# PWR.net
KiCad netlist of a schematic drawn in Altium Designer
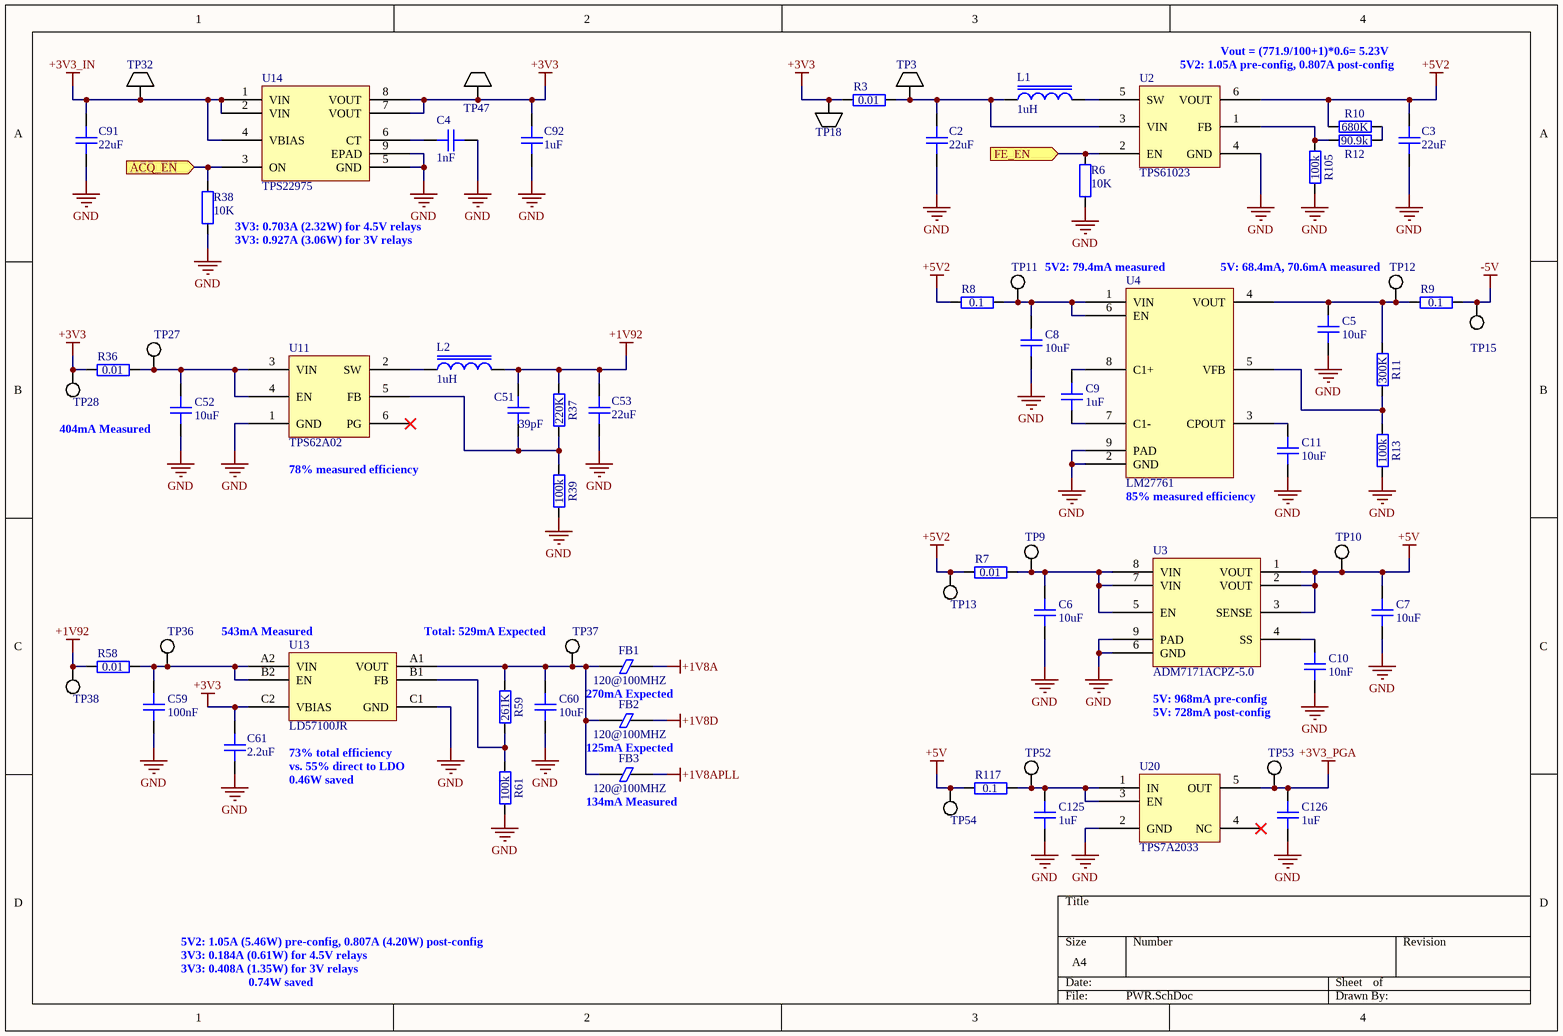
[diagram p0: PWR.SchDoc]

(export (version "E")
  (design (tool "Eeschema 10.0.6"))
  (components
    (comp (ref "C2")
      (value "22uF")
      (footprint "GEN_C_0805")
      (fields
        (field (name "HOUSE PART NUMBER") "C-22uF-0805-002")
        (field (name "MANUFACTURER") "Murata")
        (field (name "MANUFACTURER PART NUMBER") "GRM21BR61E226ME44L")
      )
      (libsource (lib "DSO") (part "CAP 22uF 25V X5R 0805"))
    )
    (comp (ref "C3")
      (value "22uF")
      (footprint "GEN_C_0805")
      (fields
        (field (name "HOUSE PART NUMBER") "C-22uF-0805-002")
        (field (name "MANUFACTURER") "Murata")
        (field (name "MANUFACTURER PART NUMBER") "GRM21BR61E226ME44L")
      )
      (libsource (lib "DSO") (part "CAP 22uF 25V X5R 0805"))
    )
    (comp (ref "C4")
      (value "1nF")
      (footprint "GEN_C_0402")
      (fields
        (field (name "MANUFACTURER") "Murata")
        (field (name "MANUFACTURER PART NUMBER") "GRM1555C1H102FA01D")
      )
      (libsource (lib "DSO") (part "CAP 1nF 50V C0G 0402"))
    )
    (comp (ref "C5")
      (value "10uF")
      (footprint "GEN_C_0603")
      (fields
        (field (name "HOUSE PART NUMBER") "C-10uF-0603-002")
        (field (name "MANUFACTURER") "Murata")
        (field (name "MANUFACTURER PART NUMBER") "GRM188R61A106ME69D")
      )
      (libsource (lib "DSO") (part "CAP 10uF 10V X5R 0603"))
    )
    (comp (ref "C6")
      (value "10uF")
      (footprint "GEN_C_0603")
      (fields
        (field (name "HOUSE PART NUMBER") "C-10uF-0603-002")
        (field (name "MANUFACTURER") "Murata")
        (field (name "MANUFACTURER PART NUMBER") "GRM188R61A106ME69D")
      )
      (libsource (lib "DSO") (part "CAP 10uF 10V X5R 0603"))
    )
    (comp (ref "C7")
      (value "10uF")
      (footprint "GEN_C_0603")
      (fields
        (field (name "HOUSE PART NUMBER") "C-10uF-0603-002")
        (field (name "MANUFACTURER") "Murata")
        (field (name "MANUFACTURER PART NUMBER") "GRM188R61A106ME69D")
      )
      (libsource (lib "DSO") (part "CAP 10uF 10V X5R 0603"))
    )
    (comp (ref "C8")
      (value "10uF")
      (footprint "GEN_C_0603")
      (fields
        (field (name "HOUSE PART NUMBER") "C-10uF-0603-002")
        (field (name "MANUFACTURER") "Murata")
        (field (name "MANUFACTURER PART NUMBER") "GRM188R61A106ME69D")
      )
      (libsource (lib "DSO") (part "CAP 10uF 10V X5R 0603"))
    )
    (comp (ref "C9")
      (value "1uF")
      (footprint "GEN_C_0402")
      (fields
        (field (name "MANUFACTURER") "Murata")
        (field (name "MANUFACTURER PART NUMBER") "GRM155R61E105KA12D")
      )
      (libsource (lib "DSO") (part "CAP 1uF 25V X5R 0402"))
    )
    (comp (ref "C10")
      (value "10nF")
      (footprint "GEN_C_0402")
      (fields
        (field (name "MANUFACTURER") "Murata")
        (field (name "HOUSE PART NUMBER") "C-10nF-0402-002")
        (field (name "MANUFACTURER PART NUMBER") "GRM155R71H103KA88J")
      )
      (libsource (lib "DSO") (part "CAP 10nF 50V X7R 0402"))
    )
    (comp (ref "C11")
      (value "10uF")
      (footprint "GEN_C_0603")
      (fields
        (field (name "HOUSE PART NUMBER") "C-10uF-0603-002")
        (field (name "MANUFACTURER") "Murata")
        (field (name "MANUFACTURER PART NUMBER") "GRM188R61A106ME69D")
      )
      (libsource (lib "DSO") (part "CAP 10uF 10V X5R 0603"))
    )
    (comp (ref "C51")
      (value "39pF")
      (footprint "GEN_C_0402")
      (fields
        (field (name "HOUSE PART NUMBER") "C-39pF-0402-002")
        (field (name "MANUFACTURER") "KEMET")
        (field (name "MANUFACTURER PART NUMBER") "C0402C390J5GACTU")
      )
      (libsource (lib "DSO") (part "CAP 39pF 50V C0G 0402"))
    )
    (comp (ref "C52")
      (value "10uF")
      (footprint "GEN_C_0603")
      (fields
        (field (name "HOUSE PART NUMBER") "C-10uF-0603-002")
        (field (name "MANUFACTURER") "Murata")
        (field (name "MANUFACTURER PART NUMBER") "GRM188R61A106ME69D")
      )
      (libsource (lib "DSO") (part "CAP 10uF 10V X5R 0603"))
    )
    (comp (ref "C53")
      (value "22uF")
      (footprint "GEN_C_0805")
      (fields
        (field (name "HOUSE PART NUMBER") "C-22uF-0805-002")
        (field (name "MANUFACTURER") "Murata")
        (field (name "MANUFACTURER PART NUMBER") "GRM21BR61E226ME44L")
      )
      (libsource (lib "DSO") (part "CAP 22uF 25V X5R 0805"))
    )
    (comp (ref "C59")
      (value "100nF")
      (footprint "GEN_C_0402")
      (fields
        (field (name "HOUSE PART NUMBER") "C-100nF-0402-002")
        (field (name "MANUFACTURER") "Murata")
        (field (name "MANUFACTURER PART NUMBER") "GCM155R71C104KA55D")
      )
      (libsource (lib "DSO") (part "CAP 100nF 16V X7R 0402"))
    )
    (comp (ref "C60")
      (value "10uF")
      (footprint "GEN_C_0603")
      (fields
        (field (name "HOUSE PART NUMBER") "C-10uF-0603-002")
        (field (name "MANUFACTURER") "Murata")
        (field (name "MANUFACTURER PART NUMBER") "GRM188R61A106ME69D")
      )
      (libsource (lib "DSO") (part "CAP 10uF 10V X5R 0603"))
    )
    (comp (ref "C61")
      (value "2.2uF")
      (footprint "GEN_C_0402")
      (fields
        (field (name "MANUFACTURER") "Taiyo Yuden")
        (field (name "MANUFACTURER PART NUMBER") "LMK105BJ225MV-F")
      )
      (libsource (lib "DSO") (part "CAP 2.2uF 10V X5R 0402"))
    )
    (comp (ref "C91")
      (value "22uF")
      (footprint "GEN_C_0805")
      (fields
        (field (name "HOUSE PART NUMBER") "C-22uF-0805-002")
        (field (name "MANUFACTURER") "Murata")
        (field (name "MANUFACTURER PART NUMBER") "GRM21BR61E226ME44L")
      )
      (libsource (lib "DSO") (part "CAP 22uF 25V X5R 0805"))
    )
    (comp (ref "C92")
      (value "1uF")
      (footprint "GEN_C_0402")
      (fields
        (field (name "MANUFACTURER") "Murata")
        (field (name "MANUFACTURER PART NUMBER") "GRM155R61E105KA12D")
      )
      (libsource (lib "DSO") (part "CAP 1uF 25V X5R 0402"))
    )
    (comp (ref "C125")
      (value "1uF")
      (footprint "GEN_C_0402")
      (fields
        (field (name "MANUFACTURER") "Murata")
        (field (name "MANUFACTURER PART NUMBER") "GRM155R61E105KA12D")
      )
      (libsource (lib "DSO") (part "CAP 1uF 25V X5R 0402"))
    )
    (comp (ref "C126")
      (value "1uF")
      (footprint "GEN_C_0402")
      (fields
        (field (name "MANUFACTURER") "Murata")
        (field (name "MANUFACTURER PART NUMBER") "GRM155R61E105KA12D")
      )
      (libsource (lib "DSO") (part "CAP 1uF 25V X5R 0402"))
    )
    (comp (ref "FB1")
      (value "120@100MHZ")
      (footprint "GEN_R_0402")
      (fields (field (name "HOUSE PART NUMBER") "BLM15PX121SN1D") (field (name "MANUFACTURER") "Murata"))
      (libsource (lib "DSO") (part "FERRITE BEAD 120 OHM 0402"))
    )
    (comp (ref "FB2")
      (value "120@100MHZ")
      (footprint "GEN_R_0402")
      (fields (field (name "HOUSE PART NUMBER") "BLM15PX121SN1D") (field (name "MANUFACTURER") "Murata"))
      (libsource (lib "DSO") (part "FERRITE BEAD 120 OHM 0402"))
    )
    (comp (ref "FB3")
      (value "120@100MHZ")
      (footprint "GEN_R_0402")
      (fields (field (name "HOUSE PART NUMBER") "BLM15PX121SN1D") (field (name "MANUFACTURER") "Murata"))
      (libsource (lib "DSO") (part "FERRITE BEAD 120 OHM 0402"))
    )
    (comp (ref "L1")
      (value "1uH")
      (footprint "GEN_L_1210")
      (fields
        (field (name "MANUFACTURER") "Murata")
        (field (name "MANUFACTURER PART NUMBER") "1277AS-H-1R0M=P2")
      )
      (libsource (lib "DSO") (part "IND 1uH 3.1A 45 MOHM 1210"))
    )
    (comp (ref "L2")
      (value "1uH")
      (footprint "GEN_L_1210")
      (fields
        (field (name "MANUFACTURER") "Murata")
        (field (name "MANUFACTURER PART NUMBER") "1277AS-H-1R0M=P2")
      )
      (libsource (lib "DSO") (part "IND 1uH 3.1A 45 MOHM 1210"))
    )
    (comp (ref "R3")
      (value "0.01")
      (footprint "GEN_R_0603")
      (fields
        (field (name "TOLERANCE") "1%")
        (field (name "HOUSE PART NUMBER") "R-0.01-0603-1%-001")
        (field (name "MANUFACTURER") "Susumu")
      )
      (libsource (lib "") (part "RES 0.01 OHM 1% 1/4W 0603_1"))
    )
    (comp (ref "R6")
      (value "10K")
      (footprint "GEN_R_0402")
      (fields
        (field (name "TOLERANCE") "1%")
        (field (name "MANUFACTURER") "Panasonic")
        (field (name "MANUFACTURER PART NUMBER") "ERJ-2RKF1002X")
      )
      (libsource (lib "") (part "RES 10K OHM 1% 1/10W 0402_1"))
    )
    (comp (ref "R7")
      (value "0.01")
      (footprint "GEN_R_0603")
      (fields
        (field (name "TOLERANCE") "1%")
        (field (name "HOUSE PART NUMBER") "R-0.01-0603-1%-001")
        (field (name "MANUFACTURER") "Susumu")
      )
      (libsource (lib "DSO") (part "RES 0.01 OHM 1% 1/4W 0603"))
    )
    (comp (ref "R8")
      (value "0.1")
      (footprint "GEN_R_0402")
      (fields
        (field (name "TOLERANCE") "1%")
        (field (name "MANUFACTURER") "Panasonic")
        (field (name "MANUFACTURER PART NUMBER") "ERJ-2BSFR10X")
      )
      (libsource (lib "DSO") (part "RES 0.1 OHM 1% 1/6W 0402"))
    )
    (comp (ref "R9")
      (value "0.1")
      (footprint "GEN_R_0402")
      (fields
        (field (name "TOLERANCE") "1%")
        (field (name "MANUFACTURER") "Panasonic")
        (field (name "MANUFACTURER PART NUMBER") "ERJ-2BSFR10X")
      )
      (libsource (lib "DSO") (part "RES 0.1 OHM 1% 1/6W 0402"))
    )
    (comp (ref "R10")
      (value "680K")
      (footprint "GEN_R_0402")
      (fields
        (field (name "TOLERANCE") "1%")
        (field (name "MANUFACTURER") "Yageo")
        (field (name "MANUFACTURER PART NUMBER") "RC0402FR-07681KL")
      )
      (libsource (lib "DSO") (part "RES 680K OHM 1% 1/16W 0402"))
    )
    (comp (ref "R11")
      (value "300K")
      (footprint "GEN_R_0402")
      (fields
        (field (name "TOLERANCE") "1%")
        (field (name "MANUFACTURER") "Panasonic")
        (field (name "MANUFACTURER PART NUMBER") "ERJ-2RKF3003X")
      )
      (libsource (lib "DSO") (part "RES 300K OHM 1% 1/10W 0402"))
    )
    (comp (ref "R12")
      (value "90.9k")
      (footprint "GEN_R_0402")
      (fields
        (field (name "TOLERANCE") "1%")
        (field (name "MANUFACTURER") "Yageo")
        (field (name "MANUFACTURER PART NUMBER") "RC0402FR-0790K9L")
      )
      (libsource (lib "DSO") (part "RES 90.9K OHM 1% 1/16W 0402"))
    )
    (comp (ref "R13")
      (value "100k")
      (footprint "GEN_R_0402")
      (fields
        (field (name "TOLERANCE") "1%")
        (field (name "HOUSE PART NUMBER") "R-100K-0402-1%-001")
        (field (name "MANUFACTURER") "Yageo")
      )
      (libsource (lib "DSO") (part "RES 100K OHM 1% 1/10W 0402"))
    )
    (comp (ref "R36")
      (value "0.01")
      (footprint "GEN_R_0603")
      (fields
        (field (name "TOLERANCE") "1%")
        (field (name "HOUSE PART NUMBER") "R-0.01-0603-1%-001")
        (field (name "MANUFACTURER") "Susumu")
      )
      (libsource (lib "DSO") (part "RES 0.01 OHM 1% 1/4W 0603"))
    )
    (comp (ref "R37")
      (value "220K")
      (footprint "GEN_R_0402")
      (fields
        (field (name "TOLERANCE") "1%")
        (field (name "MANUFACTURER") "Yageo")
        (field (name "MANUFACTURER PART NUMBER") "RC0402FR-07220KL")
      )
      (libsource (lib "DSO") (part "RES 220K OHM 1% 1/16W 0402"))
    )
    (comp (ref "R38")
      (value "10K")
      (footprint "GEN_R_0402")
      (fields
        (field (name "TOLERANCE") "1%")
        (field (name "MANUFACTURER") "Panasonic")
        (field (name "MANUFACTURER PART NUMBER") "ERJ-2RKF1002X")
      )
      (libsource (lib "DSO") (part "RES 10K OHM 1% 1/10W 0402"))
    )
    (comp (ref "R39")
      (value "100k")
      (footprint "GEN_R_0402")
      (fields
        (field (name "TOLERANCE") "1%")
        (field (name "HOUSE PART NUMBER") "R-100K-0402-1%-001")
        (field (name "MANUFACTURER") "Yageo")
      )
      (libsource (lib "DSO") (part "RES 100K OHM 1% 1/10W 0402"))
    )
    (comp (ref "R58")
      (value "0.01")
      (footprint "GEN_R_0603")
      (fields
        (field (name "TOLERANCE") "1%")
        (field (name "HOUSE PART NUMBER") "R-0.01-0603-1%-001")
        (field (name "MANUFACTURER") "Susumu")
      )
      (libsource (lib "DSO") (part "RES 0.01 OHM 1% 1/4W 0603"))
    )
    (comp (ref "R59")
      (value "261K")
      (footprint "GEN_R_0402")
      (fields
        (field (name "TOLERANCE") "1%")
        (field (name "MANUFACTURER") "Yageo")
        (field (name "MANUFACTURER PART NUMBER") "RC0402FR-07261KL")
      )
      (libsource (lib "DSO") (part "RES 261K OHM 1% 1/16W 0402"))
    )
    (comp (ref "R61")
      (value "100k")
      (footprint "GEN_R_0402")
      (fields
        (field (name "TOLERANCE") "1%")
        (field (name "HOUSE PART NUMBER") "R-100K-0402-1%-001")
        (field (name "MANUFACTURER") "Yageo")
      )
      (libsource (lib "DSO") (part "RES 100K OHM 1% 1/10W 0402"))
    )
    (comp (ref "R105")
      (value "100k")
      (footprint "GEN_R_0402")
      (fields
        (field (name "TOLERANCE") "1%")
        (field (name "HOUSE PART NUMBER") "R-100K-0402-1%-001")
        (field (name "MANUFACTURER") "Yageo")
      )
      (libsource (lib "DSO") (part "RES 100K OHM 1% 1/10W 0402"))
    )
    (comp (ref "R117")
      (value "0.1")
      (footprint "GEN_R_0402")
      (fields
        (field (name "TOLERANCE") "1%")
        (field (name "MANUFACTURER") "Panasonic")
        (field (name "MANUFACTURER PART NUMBER") "ERJ-2BSFR10X")
      )
      (libsource (lib "DSO") (part "RES 0.1 OHM 1% 1/6W 0402"))
    )
    (comp (ref "TP3")
      (value "5015")
      (footprint "KEY_5015")
      (fields (field (name "MANUFACTURER") "Keystone Electronics"))
      (libsource (lib "DSO") (part "TP KEYSTONE 5015"))
    )
    (comp (ref "TP9") (value "PCB") (footprint "GEN_TP_PCB") (libsource (lib "DSO") (part "TP PCB 1mm")))
    (comp (ref "TP10") (value "PCB") (footprint "GEN_TP_PCB") (libsource (lib "DSO") (part "TP PCB 1mm")))
    (comp (ref "TP11") (value "PCB") (footprint "GEN_TP_PCB") (libsource (lib "DSO") (part "TP PCB 1mm")))
    (comp (ref "TP12") (value "PCB") (footprint "GEN_TP_PCB") (libsource (lib "DSO") (part "TP PCB 1mm")))
    (comp (ref "TP13") (value "PCB") (footprint "GEN_TP_PCB") (libsource (lib "DSO") (part "TP PCB 1mm")))
    (comp (ref "TP15") (value "PCB") (footprint "GEN_TP_PCB") (libsource (lib "DSO") (part "TP PCB 1mm")))
    (comp (ref "TP18")
      (value "5015")
      (footprint "KEY_5015")
      (fields (field (name "MANUFACTURER") "Keystone Electronics"))
      (libsource (lib "DSO") (part "TP KEYSTONE 5015"))
    )
    (comp (ref "TP27") (value "PCB") (footprint "GEN_TP_PCB") (libsource (lib "DSO") (part "TP PCB 1mm")))
    (comp (ref "TP28") (value "PCB") (footprint "GEN_TP_PCB") (libsource (lib "DSO") (part "TP PCB 1mm")))
    (comp (ref "TP32")
      (value "5015")
      (footprint "KEY_5015")
      (fields (field (name "MANUFACTURER") "Keystone Electronics"))
      (libsource (lib "DSO") (part "TP KEYSTONE 5015"))
    )
    (comp (ref "TP36") (value "PCB") (footprint "GEN_TP_PCB") (libsource (lib "DSO") (part "TP PCB 1mm")))
    (comp (ref "TP37") (value "PCB") (footprint "GEN_TP_PCB") (libsource (lib "DSO") (part "TP PCB 1mm")))
    (comp (ref "TP38") (value "PCB") (footprint "GEN_TP_PCB") (libsource (lib "DSO") (part "TP PCB 1mm")))
    (comp (ref "TP47")
      (value "5015")
      (footprint "KEY_5015")
      (fields (field (name "MANUFACTURER") "Keystone Electronics"))
      (libsource (lib "DSO") (part "TP KEYSTONE 5015"))
    )
    (comp (ref "TP52") (value "PCB") (footprint "GEN_TP_PCB") (libsource (lib "DSO") (part "TP PCB 1mm")))
    (comp (ref "TP53") (value "PCB") (footprint "GEN_TP_PCB") (libsource (lib "DSO") (part "TP PCB 1mm")))
    (comp (ref "TP54") (value "PCB") (footprint "GEN_TP_PCB") (libsource (lib "DSO") (part "TP PCB 1mm")))
    (comp (ref "U2")
      (value "TPS61023")
      (footprint "TI_SOT563_DRL0006A")
      (fields
        (field (name "MANUFACTURER") "Texas Instruments")
        (field (name "MANUFACTURER PART NUMBER") "TPS61023DRLT")
      )
      (libsource (lib "DSO") (part "IC BOOST TPS61023"))
    )
    (comp (ref "U3")
      (value "ADM7171ACPZ-5.0")
      (footprint "AD_DFN8_CP-8-21")
      (fields
        (field (name "MANUFACTURER") "Analog Devices")
        (field (name "MANUFACTURER PART NUMBER") "ADM7171ACPZ-5.0-R7")
      )
      (libsource (lib "DSO") (part "IC LDO ADM7171ACPZ-5.0"))
    )
    (comp (ref "U4")
      (value "LM27761")
      (footprint "TI_WSON8_DSG0008A")
      (fields
        (field (name "MANUFACTURER") "Texas Instruments")
        (field (name "MANUFACTURER PART NUMBER") "LM27761DSGR")
      )
      (libsource (lib "DSO") (part "IC CPUMP LM27761"))
    )
    (comp (ref "U11")
      (value "TPS62A02")
      (footprint "TI_SOT563_DRL0006A")
      (fields
        (field (name "HOUSE PART NUMBER") "TPS62A02DRLR")
        (field (name "MANUFACTURER") "Texas Instruments")
      )
      (libsource (lib "DSO") (part "IC BUCK TPS62A02"))
    )
    (comp (ref "U13")
      (value "LD57100JR")
      (footprint "ST_FlipChip6")
      (fields (field (name "MANUFACTURER") "STMicroelectronics"))
      (libsource (lib "DSO") (part "IC LDO LD57100JR"))
    )
    (comp (ref "U14")
      (value "TPS22975")
      (footprint "TI_WSON8_DSG0008A")
      (fields
        (field (name "MANUFACTURER") "Texas Instruments")
        (field (name "MANUFACTURER PART NUMBER") "TPS22975DSGR")
      )
      (libsource (lib "DSO") (part "IC SWITCH LOAD TPS22975"))
    )
    (comp (ref "U20")
      (value "TPS7A2033")
      (footprint "GEN_SOT23_5_950_2900X1600X1450")
      (fields
        (field (name "MANUFACTURER") "Texas Instruments")
        (field (name "MANUFACTURER PART NUMBER") "TPS7A2033PDBVR")
      )
      (libsource (lib "DSO") (part "IC LDO TPS7A2033"))
    )
  )
  (nets
    (net (code "1") (name "+1V8A") (class "Default")
      (node (ref "FB1") (pin "2") (pinfunction "2_2") (pintype "passive"))
    )
    (net (code "2") (name "+1V8APLL") (class "Default")
      (node (ref "FB3") (pin "2") (pinfunction "2_2") (pintype "passive"))
    )
    (net (code "3") (name "+1V8D") (class "Default")
      (node (ref "FB2") (pin "2") (pinfunction "2_2") (pintype "passive"))
    )
    (net (code "4") (name "+1V92") (class "Default")
      (node (ref "C51") (pin "2") (pinfunction "2_2") (pintype "passive"))
      (node (ref "C53") (pin "2") (pinfunction "2_2") (pintype "passive"))
      (node (ref "L2") (pin "2") (pinfunction "2_2") (pintype "passive"))
      (node (ref "R37") (pin "2") (pinfunction "2_2") (pintype "passive"))
      (node (ref "R58") (pin "1") (pinfunction "1_1") (pintype "passive"))
      (node (ref "TP38") (pin "1") (pinfunction "1_1") (pintype "passive"))
    )
    (net (code "5") (name "+3V3") (class "Default")
      (node (ref "C61") (pin "2") (pinfunction "2_2") (pintype "passive"))
      (node (ref "C92") (pin "2") (pinfunction "2_2") (pintype "passive"))
      (node (ref "R3") (pin "2") (pinfunction "2_2") (pintype "passive"))
      (node (ref "R36") (pin "1") (pinfunction "1_1") (pintype "passive"))
      (node (ref "TP18") (pin "1") (pinfunction "1_1") (pintype "passive"))
      (node (ref "TP28") (pin "1") (pinfunction "1_1") (pintype "passive"))
      (node (ref "TP47") (pin "1") (pinfunction "1_1") (pintype "passive"))
      (node (ref "U13") (pin "C2") (pinfunction "VBIAS_C2") (pintype "passive"))
      (node (ref "U14") (pin "7") (pinfunction "VOUT_7") (pintype "passive"))
      (node (ref "U14") (pin "8") (pinfunction "VOUT_8") (pintype "passive"))
    )
    (net (code "6") (name "+3V3_IN") (class "Default")
      (node (ref "C91") (pin "2") (pinfunction "2_2") (pintype "passive"))
      (node (ref "TP32") (pin "1") (pinfunction "1_1") (pintype "passive"))
      (node (ref "U14") (pin "1") (pinfunction "VIN_1") (pintype "passive"))
      (node (ref "U14") (pin "2") (pinfunction "VIN_2") (pintype "passive"))
      (node (ref "U14") (pin "4") (pinfunction "VBIAS_4") (pintype "passive"))
    )
    (net (code "7") (name "+3V3_PGA") (class "Default")
      (node (ref "C126") (pin "2") (pinfunction "2_2") (pintype "passive"))
      (node (ref "TP53") (pin "1") (pinfunction "1_1") (pintype "passive"))
      (node (ref "U20") (pin "5") (pinfunction "OUT_5") (pintype "power_in"))
    )
    (net (code "8") (name "+5V") (class "Default")
      (node (ref "C7") (pin "2") (pinfunction "2_2") (pintype "passive"))
      (node (ref "R117") (pin "1") (pinfunction "1_1") (pintype "passive"))
      (node (ref "TP10") (pin "1") (pinfunction "1_1") (pintype "passive"))
      (node (ref "TP54") (pin "1") (pinfunction "1_1") (pintype "passive"))
      (node (ref "U3") (pin "1") (pinfunction "VOUT_1") (pintype "power_in"))
      (node (ref "U3") (pin "2") (pinfunction "VOUT_2") (pintype "power_in"))
      (node (ref "U3") (pin "3") (pinfunction "SENSE_3") (pintype "passive"))
    )
    (net (code "9") (name "+5V2") (class "Default")
      (node (ref "C3") (pin "2") (pinfunction "2_2") (pintype "passive"))
      (node (ref "R10") (pin "2") (pinfunction "2_2") (pintype "passive"))
      (node (ref "R7") (pin "1") (pinfunction "1_1") (pintype "passive"))
      (node (ref "R8") (pin "1") (pinfunction "1_1") (pintype "passive"))
      (node (ref "TP13") (pin "1") (pinfunction "1_1") (pintype "passive"))
      (node (ref "U2") (pin "6") (pinfunction "VOUT_6") (pintype "passive"))
    )
    (net (code "10") (name "-5V") (class "Default")
      (node (ref "R9") (pin "2") (pinfunction "2_2") (pintype "passive"))
      (node (ref "TP15") (pin "1") (pinfunction "1_1") (pintype "passive"))
    )
    (net (code "11") (name "/ACQ_EN") (class "Default")
      (node (ref "R38") (pin "2") (pinfunction "2_2") (pintype "passive"))
      (node (ref "U14") (pin "3") (pinfunction "ON_3") (pintype "passive"))
    )
    (net (code "12") (name "/FE_EN") (class "Default")
      (node (ref "R6") (pin "1") (pinfunction "1_1") (pintype "passive"))
      (node (ref "U2") (pin "2") (pinfunction "EN_2") (pintype "passive"))
    )
    (net (code "13") (name "GND") (class "Default")
      (node (ref "C10") (pin "1") (pinfunction "1_1") (pintype "passive"))
      (node (ref "C11") (pin "1") (pinfunction "1_1") (pintype "passive"))
      (node (ref "C125") (pin "1") (pinfunction "1_1") (pintype "passive"))
      (node (ref "C126") (pin "1") (pinfunction "1_1") (pintype "passive"))
      (node (ref "C2") (pin "1") (pinfunction "1_1") (pintype "passive"))
      (node (ref "C3") (pin "1") (pinfunction "1_1") (pintype "passive"))
      (node (ref "C4") (pin "1") (pinfunction "1_1") (pintype "passive"))
      (node (ref "C5") (pin "1") (pinfunction "1_1") (pintype "passive"))
      (node (ref "C52") (pin "1") (pinfunction "1_1") (pintype "passive"))
      (node (ref "C53") (pin "1") (pinfunction "1_1") (pintype "passive"))
      (node (ref "C59") (pin "1") (pinfunction "1_1") (pintype "passive"))
      (node (ref "C6") (pin "1") (pinfunction "1_1") (pintype "passive"))
      (node (ref "C60") (pin "1") (pinfunction "1_1") (pintype "passive"))
      (node (ref "C61") (pin "1") (pinfunction "1_1") (pintype "passive"))
      (node (ref "C7") (pin "1") (pinfunction "1_1") (pintype "passive"))
      (node (ref "C8") (pin "1") (pinfunction "1_1") (pintype "passive"))
      (node (ref "C91") (pin "1") (pinfunction "1_1") (pintype "passive"))
      (node (ref "C92") (pin "1") (pinfunction "1_1") (pintype "passive"))
      (node (ref "R105") (pin "1") (pinfunction "1_1") (pintype "passive"))
      (node (ref "R13") (pin "1") (pinfunction "1_1") (pintype "passive"))
      (node (ref "R38") (pin "1") (pinfunction "1_1") (pintype "passive"))
      (node (ref "R39") (pin "1") (pinfunction "1_1") (pintype "passive"))
      (node (ref "R6") (pin "2") (pinfunction "2_2") (pintype "passive"))
      (node (ref "R61") (pin "1") (pinfunction "1_1") (pintype "passive"))
      (node (ref "U11") (pin "1") (pinfunction "GND_1") (pintype "power_in"))
      (node (ref "U13") (pin "C1") (pinfunction "GND_C1") (pintype "passive"))
      (node (ref "U14") (pin "5") (pinfunction "GND_5") (pintype "passive"))
      (node (ref "U14") (pin "9") (pinfunction "EPAD_9") (pintype "passive"))
      (node (ref "U2") (pin "4") (pinfunction "GND_4") (pintype "power_in"))
      (node (ref "U20") (pin "2") (pinfunction "GND_2") (pintype "power_in"))
      (node (ref "U3") (pin "6") (pinfunction "GND_6") (pintype "power_in"))
      (node (ref "U3") (pin "9") (pinfunction "PAD_9") (pintype "passive"))
      (node (ref "U4") (pin "2") (pinfunction "GND_2") (pintype "power_in"))
      (node (ref "U4") (pin "9") (pinfunction "PAD_9") (pintype "power_in"))
    )
    (net (code "14") (name "Net-(R10-Pad1)") (class "Default")
      (node (ref "R10") (pin "1") (pinfunction "1_1") (pintype "passive"))
      (node (ref "R12") (pin "2") (pinfunction "2_2") (pintype "passive"))
    )
    (net (code "15") (name "Net-(U2-FB)") (class "Default")
      (node (ref "R105") (pin "2") (pinfunction "2_2") (pintype "passive"))
      (node (ref "R12") (pin "1") (pinfunction "1_1") (pintype "passive"))
      (node (ref "U2") (pin "1") (pinfunction "FB_1") (pintype "passive"))
    )
    (net (code "16") (name "Net-(U2-SW)") (class "Default")
      (node (ref "L1") (pin "2") (pinfunction "2_2") (pintype "passive"))
      (node (ref "U2") (pin "5") (pinfunction "SW_5") (pintype "passive"))
    )
    (net (code "17") (name "Net-(U2-VIN)") (class "Default")
      (node (ref "C2") (pin "2") (pinfunction "2_2") (pintype "passive"))
      (node (ref "L1") (pin "1") (pinfunction "1_1") (pintype "passive"))
      (node (ref "R3") (pin "1") (pinfunction "1_1") (pintype "passive"))
      (node (ref "TP3") (pin "1") (pinfunction "1_1") (pintype "passive"))
      (node (ref "U2") (pin "3") (pinfunction "VIN_3") (pintype "power_in"))
    )
    (net (code "18") (name "Net-(U3-EN)") (class "Default")
      (node (ref "C6") (pin "2") (pinfunction "2_2") (pintype "passive"))
      (node (ref "R7") (pin "2") (pinfunction "2_2") (pintype "passive"))
      (node (ref "TP9") (pin "1") (pinfunction "1_1") (pintype "passive"))
      (node (ref "U3") (pin "5") (pinfunction "EN_5") (pintype "passive"))
      (node (ref "U3") (pin "7") (pinfunction "VIN_7") (pintype "power_in"))
      (node (ref "U3") (pin "8") (pinfunction "VIN_8") (pintype "power_in"))
    )
    (net (code "19") (name "Net-(U3-SS)") (class "Default")
      (node (ref "C10") (pin "2") (pinfunction "2_2") (pintype "passive"))
      (node (ref "U3") (pin "4") (pinfunction "SS_4") (pintype "passive"))
    )
    (net (code "20") (name "Net-(U4-C1+)") (class "Default")
      (node (ref "C9") (pin "2") (pinfunction "2_2") (pintype "passive"))
      (node (ref "U4") (pin "8") (pinfunction "C1+_8") (pintype "passive"))
    )
    (net (code "21") (name "Net-(U4-C1-)") (class "Default")
      (node (ref "C9") (pin "1") (pinfunction "1_1") (pintype "passive"))
      (node (ref "U4") (pin "7") (pinfunction "C1-_7") (pintype "passive"))
    )
    (net (code "22") (name "Net-(U4-CPOUT)") (class "Default")
      (node (ref "C11") (pin "2") (pinfunction "2_2") (pintype "passive"))
      (node (ref "U4") (pin "3") (pinfunction "CPOUT_3") (pintype "passive"))
    )
    (net (code "23") (name "Net-(U4-EN)") (class "Default")
      (node (ref "C8") (pin "2") (pinfunction "2_2") (pintype "passive"))
      (node (ref "R8") (pin "2") (pinfunction "2_2") (pintype "passive"))
      (node (ref "TP11") (pin "1") (pinfunction "1_1") (pintype "passive"))
      (node (ref "U4") (pin "1") (pinfunction "VIN_1") (pintype "power_in"))
      (node (ref "U4") (pin "6") (pinfunction "EN_6") (pintype "passive"))
    )
    (net (code "24") (name "Net-(U4-VFB)") (class "Default")
      (node (ref "R11") (pin "1") (pinfunction "1_1") (pintype "passive"))
      (node (ref "R13") (pin "2") (pinfunction "2_2") (pintype "passive"))
      (node (ref "U4") (pin "5") (pinfunction "VFB_5") (pintype "passive"))
    )
    (net (code "25") (name "Net-(U4-VOUT)") (class "Default")
      (node (ref "C5") (pin "2") (pinfunction "2_2") (pintype "passive"))
      (node (ref "R11") (pin "2") (pinfunction "2_2") (pintype "passive"))
      (node (ref "R9") (pin "1") (pinfunction "1_1") (pintype "passive"))
      (node (ref "TP12") (pin "1") (pinfunction "1_1") (pintype "passive"))
      (node (ref "U4") (pin "4") (pinfunction "VOUT_4") (pintype "power_in"))
    )
    (net (code "26") (name "Net-(U11-EN)") (class "Default")
      (node (ref "C52") (pin "2") (pinfunction "2_2") (pintype "passive"))
      (node (ref "R36") (pin "2") (pinfunction "2_2") (pintype "passive"))
      (node (ref "TP27") (pin "1") (pinfunction "1_1") (pintype "passive"))
      (node (ref "U11") (pin "3") (pinfunction "VIN_3") (pintype "power_in"))
      (node (ref "U11") (pin "4") (pinfunction "EN_4") (pintype "passive"))
    )
    (net (code "27") (name "Net-(U11-FB)") (class "Default")
      (node (ref "C51") (pin "1") (pinfunction "1_1") (pintype "passive"))
      (node (ref "R37") (pin "1") (pinfunction "1_1") (pintype "passive"))
      (node (ref "R39") (pin "2") (pinfunction "2_2") (pintype "passive"))
      (node (ref "U11") (pin "5") (pinfunction "FB_5") (pintype "passive"))
    )
    (net (code "28") (name "Net-(U11-SW)") (class "Default")
      (node (ref "L2") (pin "1") (pinfunction "1_1") (pintype "passive"))
      (node (ref "U11") (pin "2") (pinfunction "SW_2") (pintype "passive"))
    )
    (net (code "29") (name "Net-(U13-EN)") (class "Default")
      (node (ref "C59") (pin "2") (pinfunction "2_2") (pintype "passive"))
      (node (ref "R58") (pin "2") (pinfunction "2_2") (pintype "passive"))
      (node (ref "TP36") (pin "1") (pinfunction "1_1") (pintype "passive"))
      (node (ref "U13") (pin "A2") (pinfunction "VIN_A2") (pintype "passive"))
      (node (ref "U13") (pin "B2") (pinfunction "EN_B2") (pintype "passive"))
    )
    (net (code "30") (name "Net-(U13-FB)") (class "Default")
      (node (ref "R59") (pin "1") (pinfunction "1_1") (pintype "passive"))
      (node (ref "R61") (pin "2") (pinfunction "2_2") (pintype "passive"))
      (node (ref "U13") (pin "B1") (pinfunction "FB_B1") (pintype "passive"))
    )
    (net (code "31") (name "Net-(U13-VOUT)") (class "Default")
      (node (ref "C60") (pin "2") (pinfunction "2_2") (pintype "passive"))
      (node (ref "FB1") (pin "1") (pinfunction "1_1") (pintype "passive"))
      (node (ref "FB2") (pin "1") (pinfunction "1_1") (pintype "passive"))
      (node (ref "FB3") (pin "1") (pinfunction "1_1") (pintype "passive"))
      (node (ref "R59") (pin "2") (pinfunction "2_2") (pintype "passive"))
      (node (ref "TP37") (pin "1") (pinfunction "1_1") (pintype "passive"))
      (node (ref "U13") (pin "A1") (pinfunction "VOUT_A1") (pintype "passive"))
    )
    (net (code "32") (name "Net-(U14-CT)") (class "Default")
      (node (ref "C4") (pin "2") (pinfunction "2_2") (pintype "passive"))
      (node (ref "U14") (pin "6") (pinfunction "CT_6") (pintype "passive"))
    )
    (net (code "33") (name "Net-(U20-EN)") (class "Default")
      (node (ref "C125") (pin "2") (pinfunction "2_2") (pintype "passive"))
      (node (ref "R117") (pin "2") (pinfunction "2_2") (pintype "passive"))
      (node (ref "TP52") (pin "1") (pinfunction "1_1") (pintype "passive"))
      (node (ref "U20") (pin "1") (pinfunction "IN_1") (pintype "power_in"))
      (node (ref "U20") (pin "3") (pinfunction "EN_3") (pintype "passive"))
    )
    (net (code "34") (name "unconnected-(U11-PG-Pad6)") (class "Default")
      (node (ref "U11") (pin "6") (pinfunction "PG_6") (pintype "passive+no_connect"))
    )
    (net (code "35") (name "unconnected-(U20-NC-Pad4)") (class "Default")
      (node (ref "U20") (pin "4") (pinfunction "NC_4") (pintype "passive+no_connect"))
    )
  )
)
